# battery_module.net
KiCad netlist of a schematic drawn in Altium Designer
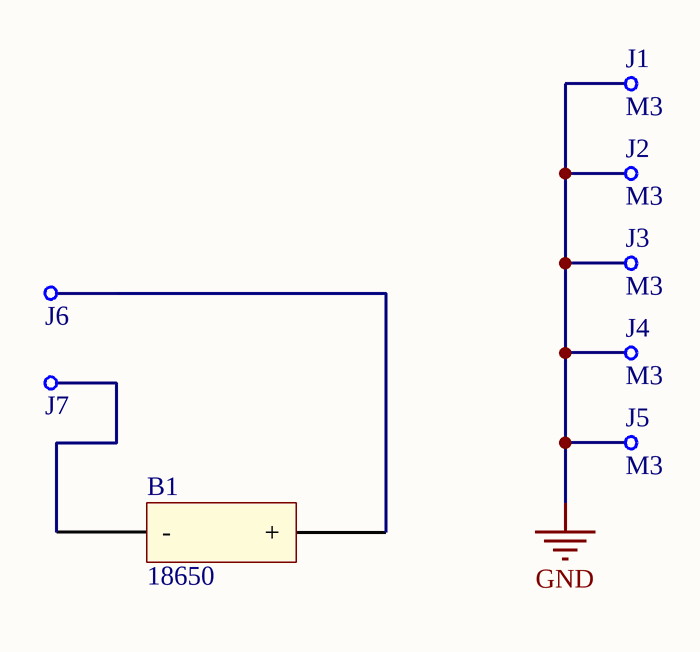
[diagram p0: battery_module.SchDoc]

(export (version "E")
  (design (tool "Eeschema 10.0.6"))
  (components
    (comp (ref "B1") (value "18650") (footprint "18650") (libsource (lib "rys_component_lib") (part "18650")))
    (comp (ref "J1")
      (value "M3")
      (footprint "HOLE_M3")
      (description "Power Element with threaded hole M3")
      (libsource (lib "Connectors") (part "Screw M3 Hole"))
    )
    (comp (ref "J2")
      (value "M3")
      (footprint "HOLE_M3")
      (description "Power Element with threaded hole M3")
      (libsource (lib "Connectors") (part "Screw M3 Hole"))
    )
    (comp (ref "J3")
      (value "M3")
      (footprint "HOLE_M3")
      (description "Power Element with threaded hole M3")
      (libsource (lib "Connectors") (part "Screw M3 Hole"))
    )
    (comp (ref "J4")
      (value "M3")
      (footprint "HOLE_M3")
      (description "Power Element with threaded hole M3")
      (libsource (lib "Connectors") (part "Screw M3 Hole"))
    )
    (comp (ref "J5")
      (value "M3")
      (footprint "HOLE_M3")
      (description "Power Element with threaded hole M3")
      (libsource (lib "Connectors") (part "Screw M3 Hole"))
    )
    (comp (ref "J6")
      (value "Pad")
      (footprint "Other-Connectors:Hole 1.6mm")
      (libsource (lib "Connectors") (part "Pad"))
    )
    (comp (ref "J7")
      (value "Pad")
      (footprint "Other-Connectors:Hole 1.6mm")
      (libsource (lib "Connectors") (part "Pad"))
    )
  )
  (nets
    (net (code "1") (name "GND") (class "Default")
      (node (ref "J1") (pin "1") (pintype "passive"))
      (node (ref "J2") (pin "1") (pintype "passive"))
      (node (ref "J3") (pin "1") (pintype "passive"))
      (node (ref "J4") (pin "1") (pintype "passive"))
      (node (ref "J5") (pin "1") (pintype "passive"))
    )
    (net (code "2") (name "Net-(B1-+)") (class "Default")
      (node (ref "B1") (pin "1") (pinfunction "+_1") (pintype "passive"))
      (node (ref "J6") (pin "1") (pintype "passive"))
    )
    (net (code "3") (name "Net-(B1--)") (class "Default")
      (node (ref "B1") (pin "2") (pinfunction "-_2") (pintype "passive"))
      (node (ref "J7") (pin "1") (pintype "passive"))
    )
  )
)
